# ConnectorSch.net
KiCad netlist of a schematic drawn in Altium Designer
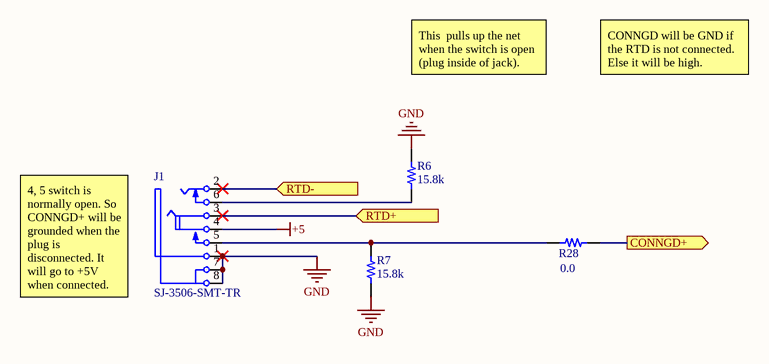
[diagram p0: ConnectorSch.SchDoc]

(export (version "E")
  (design (tool "Eeschema 10.0.6"))
  (components
    (comp (ref "J1")
      (value "SJ-3506-SMT-TR")
      (footprint "CUI-SJ-3506-SMT-TR_V")
      (libsource (lib "Altium Content Vault") (part "JACK-3CD6-TN"))
    )
    (comp (ref "R6")
      (value "15.8k")
      (footprint "RES 0805/2012")
      (description "RES SMD 15.8K OHM 1% 1/8W 0805")
      (fields
        (field (name "PART NUMBER") "ERJ-6ENF1582V")
        (field (name "MANUFACTURER") "Panasonic Electronic Components")
      )
      (libsource (lib "Celestial Library Database") (part "Resistor"))
    )
    (comp (ref "R7")
      (value "15.8k")
      (footprint "RES 0805/2012")
      (description "RES SMD 15.8K OHM 1% 1/8W 0805")
      (fields
        (field (name "PART NUMBER") "ERJ-6ENF1582V")
        (field (name "MANUFACTURER") "Panasonic Electronic Components")
      )
      (libsource (lib "Celestial Library Database") (part "Resistor"))
    )
    (comp (ref "R28")
      (value "0.0")
      (footprint "RES 1206/3216")
      (description "RES SMD 0.0 OHM JUMPER 1/4W 1206")
      (fields
        (field (name "PART NUMBER") "ERJ-8GEY0R00V")
        (field (name "MANUFACTURER") "Panasonic Electronic Components")
      )
      (libsource (lib "Celestial Library Database") (part "Resistor"))
    )
  )
  (nets
    (net (code "1") (name "+5") (class "Default")
      (node (ref "J1") (pin "4") (pinfunction "IR_4") (pintype "passive"))
    )
    (net (code "2") (name "/CONNGD+") (class "Default")
      (node (ref "R28") (pin "2") (pinfunction "2_2") (pintype "passive"))
    )
    (net (code "3") (name "/RTD+") (class "Default")
      (node (ref "J1") (pin "3") (pinfunction "R_3") (pintype "passive+no_connect"))
    )
    (net (code "4") (name "/RTD-") (class "Default")
      (node (ref "J1") (pin "2") (pinfunction "T_2") (pintype "passive+no_connect"))
    )
    (net (code "5") (name "GND") (class "Default")
      (node (ref "J1") (pin "1") (pinfunction "S_1") (pintype "passive"))
      (node (ref "J1") (pin "7") (pinfunction "SHLD1_7") (pintype "passive"))
      (node (ref "J1") (pin "8") (pinfunction "SHLD2_8") (pintype "passive"))
      (node (ref "R6") (pin "1") (pinfunction "1_1") (pintype "passive"))
      (node (ref "R7") (pin "1") (pinfunction "1_1") (pintype "passive"))
    )
    (net (code "6") (name "Net-(J1-RN)") (class "Default")
      (node (ref "J1") (pin "5") (pinfunction "RN_5") (pintype "passive"))
      (node (ref "R28") (pin "1") (pinfunction "1_1") (pintype "passive"))
      (node (ref "R7") (pin "2") (pinfunction "2_2") (pintype "passive"))
    )
    (net (code "7") (name "Net-(J1-TN)") (class "Default")
      (node (ref "J1") (pin "6") (pinfunction "TN_6") (pintype "passive"))
      (node (ref "R6") (pin "2") (pinfunction "2_2") (pintype "passive"))
    )
  )
)
